# Cell_Balancing_Interface.net
KiCad netlist of a schematic drawn in Altium Designer
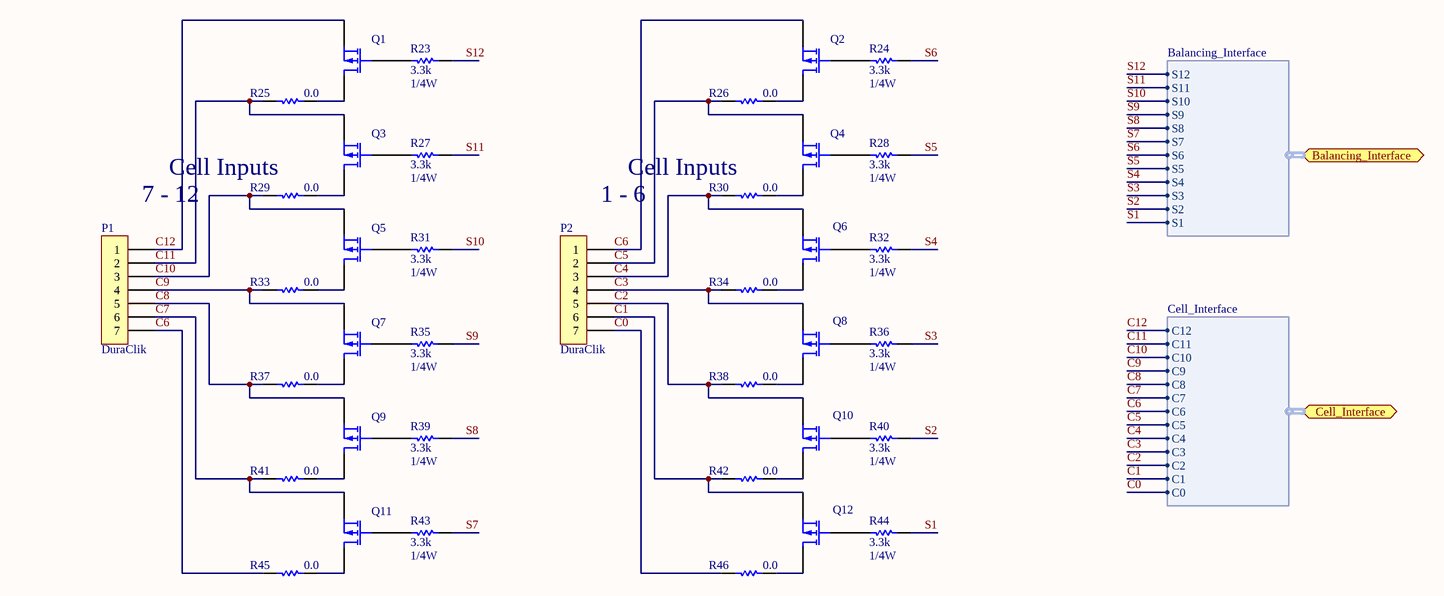
[diagram p0: Cell+Balancing_Interface.SchDoc]

(export (version "E")
  (design (tool "Eeschema 10.0.6"))
  (components
    (comp (ref "P1")
      (value "CONN 7POS DURA-CLIK 0.079\"")
      (description "7 Positions Header Connector 0.079\" (2.00mm) Surface Mount Tin")
      (fields (field (name "SERIES") "DuraClik"))
      (libsource (lib "Schematic Diagrams") (part "CONN 7POS DURA-CLIK 0.079{dblquote}"))
    )
    (comp (ref "P2")
      (value "CONN 7POS DURA-CLIK 0.079\"")
      (description "7 Positions Header Connector 0.079\" (2.00mm) Surface Mount Tin")
      (fields (field (name "SERIES") "DuraClik"))
      (libsource (lib "Schematic Diagrams") (part "CONN 7POS DURA-CLIK 0.079{dblquote}"))
    )
    (comp (ref "Q1")
      (value "MOSFET P-CH 16V 2.5A X2-DFN2015")
      (description "P-Channel 16V 2.5A (Ta) 650mW (Ta) Surface Mount X2-DFN2015-3")
      (libsource (lib "Schematic Diagrams") (part "MOSFET P-CH 16V 2.5A X2-DFN2015"))
    )
    (comp (ref "Q2")
      (value "MOSFET P-CH 16V 2.5A X2-DFN2015")
      (description "P-Channel 16V 2.5A (Ta) 650mW (Ta) Surface Mount X2-DFN2015-3")
      (libsource (lib "Schematic Diagrams") (part "MOSFET P-CH 16V 2.5A X2-DFN2015"))
    )
    (comp (ref "Q3")
      (value "MOSFET P-CH 16V 2.5A X2-DFN2015")
      (description "P-Channel 16V 2.5A (Ta) 650mW (Ta) Surface Mount X2-DFN2015-3")
      (libsource (lib "Schematic Diagrams") (part "MOSFET P-CH 16V 2.5A X2-DFN2015"))
    )
    (comp (ref "Q4")
      (value "MOSFET P-CH 16V 2.5A X2-DFN2015")
      (description "P-Channel 16V 2.5A (Ta) 650mW (Ta) Surface Mount X2-DFN2015-3")
      (libsource (lib "Schematic Diagrams") (part "MOSFET P-CH 16V 2.5A X2-DFN2015"))
    )
    (comp (ref "Q5")
      (value "MOSFET P-CH 16V 2.5A X2-DFN2015")
      (description "P-Channel 16V 2.5A (Ta) 650mW (Ta) Surface Mount X2-DFN2015-3")
      (libsource (lib "Schematic Diagrams") (part "MOSFET P-CH 16V 2.5A X2-DFN2015"))
    )
    (comp (ref "Q6")
      (value "MOSFET P-CH 16V 2.5A X2-DFN2015")
      (description "P-Channel 16V 2.5A (Ta) 650mW (Ta) Surface Mount X2-DFN2015-3")
      (libsource (lib "Schematic Diagrams") (part "MOSFET P-CH 16V 2.5A X2-DFN2015"))
    )
    (comp (ref "Q7")
      (value "MOSFET P-CH 16V 2.5A X2-DFN2015")
      (description "P-Channel 16V 2.5A (Ta) 650mW (Ta) Surface Mount X2-DFN2015-3")
      (libsource (lib "Schematic Diagrams") (part "MOSFET P-CH 16V 2.5A X2-DFN2015"))
    )
    (comp (ref "Q8")
      (value "MOSFET P-CH 16V 2.5A X2-DFN2015")
      (description "P-Channel 16V 2.5A (Ta) 650mW (Ta) Surface Mount X2-DFN2015-3")
      (libsource (lib "Schematic Diagrams") (part "MOSFET P-CH 16V 2.5A X2-DFN2015"))
    )
    (comp (ref "Q9")
      (value "MOSFET P-CH 16V 2.5A X2-DFN2015")
      (description "P-Channel 16V 2.5A (Ta) 650mW (Ta) Surface Mount X2-DFN2015-3")
      (libsource (lib "Schematic Diagrams") (part "MOSFET P-CH 16V 2.5A X2-DFN2015"))
    )
    (comp (ref "Q10")
      (value "MOSFET P-CH 16V 2.5A X2-DFN2015")
      (description "P-Channel 16V 2.5A (Ta) 650mW (Ta) Surface Mount X2-DFN2015-3")
      (libsource (lib "Schematic Diagrams") (part "MOSFET P-CH 16V 2.5A X2-DFN2015"))
    )
    (comp (ref "Q11")
      (value "MOSFET P-CH 16V 2.5A X2-DFN2015")
      (description "P-Channel 16V 2.5A (Ta) 650mW (Ta) Surface Mount X2-DFN2015-3")
      (libsource (lib "Schematic Diagrams") (part "MOSFET P-CH 16V 2.5A X2-DFN2015"))
    )
    (comp (ref "Q12")
      (value "MOSFET P-CH 16V 2.5A X2-DFN2015")
      (description "P-Channel 16V 2.5A (Ta) 650mW (Ta) Surface Mount X2-DFN2015-3")
      (libsource (lib "Schematic Diagrams") (part "MOSFET P-CH 16V 2.5A X2-DFN2015"))
    )
    (comp (ref "R23")
      (value "RES 3.3K OHM 1% 1/4W 0603")
      (footprint "RES, 0603")
      (fields
        (field (name "TOLERANCE") "±1%")
        (field (name "RESISTANCE") "3.3k")
        (field (name "POWER") "1/4W")
      )
      (libsource (lib "Schematic Diagrams") (part "RES 3.3K OHM 1% 1/4W 0603"))
    )
    (comp (ref "R24")
      (value "RES 3.3K OHM 1% 1/4W 0603")
      (footprint "RES, 0603")
      (fields
        (field (name "TOLERANCE") "±1%")
        (field (name "RESISTANCE") "3.3k")
        (field (name "POWER") "1/4W")
      )
      (libsource (lib "Schematic Diagrams") (part "RES 3.3K OHM 1% 1/4W 0603"))
    )
    (comp (ref "R25")
      (value "RES 0.0 OHM 1/4W 0603")
      (footprint "RES, 0603")
      (description "RES SMD 0.0 OHM JUMPER 1/4W 0603")
      (fields (field (name "RESISTANCE") "0.0"))
      (libsource (lib "Schematic Diagrams") (part "RES 0.0 OHM 1/4W 0603"))
    )
    (comp (ref "R26")
      (value "RES 0.0 OHM 1/4W 0603")
      (footprint "RES, 0603")
      (description "RES SMD 0.0 OHM JUMPER 1/4W 0603")
      (fields (field (name "RESISTANCE") "0.0"))
      (libsource (lib "Schematic Diagrams") (part "RES 0.0 OHM 1/4W 0603"))
    )
    (comp (ref "R27")
      (value "RES 3.3K OHM 1% 1/4W 0603")
      (footprint "RES, 0603")
      (fields
        (field (name "TOLERANCE") "±1%")
        (field (name "RESISTANCE") "3.3k")
        (field (name "POWER") "1/4W")
      )
      (libsource (lib "Schematic Diagrams") (part "RES 3.3K OHM 1% 1/4W 0603"))
    )
    (comp (ref "R28")
      (value "RES 3.3K OHM 1% 1/4W 0603")
      (footprint "RES, 0603")
      (fields
        (field (name "TOLERANCE") "±1%")
        (field (name "RESISTANCE") "3.3k")
        (field (name "POWER") "1/4W")
      )
      (libsource (lib "Schematic Diagrams") (part "RES 3.3K OHM 1% 1/4W 0603"))
    )
    (comp (ref "R29")
      (value "RES 0.0 OHM 1/4W 0603")
      (footprint "RES, 0603")
      (description "RES SMD 0.0 OHM JUMPER 1/4W 0603")
      (fields (field (name "RESISTANCE") "0.0"))
      (libsource (lib "Schematic Diagrams") (part "RES 0.0 OHM 1/4W 0603"))
    )
    (comp (ref "R30")
      (value "RES 0.0 OHM 1/4W 0603")
      (footprint "RES, 0603")
      (description "RES SMD 0.0 OHM JUMPER 1/4W 0603")
      (fields (field (name "RESISTANCE") "0.0"))
      (libsource (lib "Schematic Diagrams") (part "RES 0.0 OHM 1/4W 0603"))
    )
    (comp (ref "R31")
      (value "RES 3.3K OHM 1% 1/4W 0603")
      (footprint "RES, 0603")
      (fields
        (field (name "TOLERANCE") "±1%")
        (field (name "RESISTANCE") "3.3k")
        (field (name "POWER") "1/4W")
      )
      (libsource (lib "Schematic Diagrams") (part "RES 3.3K OHM 1% 1/4W 0603"))
    )
    (comp (ref "R32")
      (value "RES 3.3K OHM 1% 1/4W 0603")
      (footprint "RES, 0603")
      (fields
        (field (name "TOLERANCE") "±1%")
        (field (name "RESISTANCE") "3.3k")
        (field (name "POWER") "1/4W")
      )
      (libsource (lib "Schematic Diagrams") (part "RES 3.3K OHM 1% 1/4W 0603"))
    )
    (comp (ref "R33")
      (value "RES 0.0 OHM 1/4W 0603")
      (footprint "RES, 0603")
      (description "RES SMD 0.0 OHM JUMPER 1/4W 0603")
      (fields (field (name "RESISTANCE") "0.0"))
      (libsource (lib "Schematic Diagrams") (part "RES 0.0 OHM 1/4W 0603"))
    )
    (comp (ref "R34")
      (value "RES 0.0 OHM 1/4W 0603")
      (footprint "RES, 0603")
      (description "RES SMD 0.0 OHM JUMPER 1/4W 0603")
      (fields (field (name "RESISTANCE") "0.0"))
      (libsource (lib "Schematic Diagrams") (part "RES 0.0 OHM 1/4W 0603"))
    )
    (comp (ref "R35")
      (value "RES 3.3K OHM 1% 1/4W 0603")
      (footprint "RES, 0603")
      (fields
        (field (name "TOLERANCE") "±1%")
        (field (name "RESISTANCE") "3.3k")
        (field (name "POWER") "1/4W")
      )
      (libsource (lib "Schematic Diagrams") (part "RES 3.3K OHM 1% 1/4W 0603"))
    )
    (comp (ref "R36")
      (value "RES 3.3K OHM 1% 1/4W 0603")
      (footprint "RES, 0603")
      (fields
        (field (name "TOLERANCE") "±1%")
        (field (name "RESISTANCE") "3.3k")
        (field (name "POWER") "1/4W")
      )
      (libsource (lib "Schematic Diagrams") (part "RES 3.3K OHM 1% 1/4W 0603"))
    )
    (comp (ref "R37")
      (value "RES 0.0 OHM 1/4W 0603")
      (footprint "RES, 0603")
      (description "RES SMD 0.0 OHM JUMPER 1/4W 0603")
      (fields (field (name "RESISTANCE") "0.0"))
      (libsource (lib "Schematic Diagrams") (part "RES 0.0 OHM 1/4W 0603"))
    )
    (comp (ref "R38")
      (value "RES 0.0 OHM 1/4W 0603")
      (footprint "RES, 0603")
      (description "RES SMD 0.0 OHM JUMPER 1/4W 0603")
      (fields (field (name "RESISTANCE") "0.0"))
      (libsource (lib "Schematic Diagrams") (part "RES 0.0 OHM 1/4W 0603"))
    )
    (comp (ref "R39")
      (value "RES 3.3K OHM 1% 1/4W 0603")
      (footprint "RES, 0603")
      (fields
        (field (name "TOLERANCE") "±1%")
        (field (name "RESISTANCE") "3.3k")
        (field (name "POWER") "1/4W")
      )
      (libsource (lib "Schematic Diagrams") (part "RES 3.3K OHM 1% 1/4W 0603"))
    )
    (comp (ref "R40")
      (value "RES 3.3K OHM 1% 1/4W 0603")
      (footprint "RES, 0603")
      (fields
        (field (name "TOLERANCE") "±1%")
        (field (name "RESISTANCE") "3.3k")
        (field (name "POWER") "1/4W")
      )
      (libsource (lib "Schematic Diagrams") (part "RES 3.3K OHM 1% 1/4W 0603"))
    )
    (comp (ref "R41")
      (value "RES 0.0 OHM 1/4W 0603")
      (footprint "RES, 0603")
      (description "RES SMD 0.0 OHM JUMPER 1/4W 0603")
      (fields (field (name "RESISTANCE") "0.0"))
      (libsource (lib "Schematic Diagrams") (part "RES 0.0 OHM 1/4W 0603"))
    )
    (comp (ref "R42")
      (value "RES 0.0 OHM 1/4W 0603")
      (footprint "RES, 0603")
      (description "RES SMD 0.0 OHM JUMPER 1/4W 0603")
      (fields (field (name "RESISTANCE") "0.0"))
      (libsource (lib "Schematic Diagrams") (part "RES 0.0 OHM 1/4W 0603"))
    )
    (comp (ref "R43")
      (value "RES 3.3K OHM 1% 1/4W 0603")
      (footprint "RES, 0603")
      (fields
        (field (name "TOLERANCE") "±1%")
        (field (name "RESISTANCE") "3.3k")
        (field (name "POWER") "1/4W")
      )
      (libsource (lib "Schematic Diagrams") (part "RES 3.3K OHM 1% 1/4W 0603"))
    )
    (comp (ref "R44")
      (value "RES 3.3K OHM 1% 1/4W 0603")
      (footprint "RES, 0603")
      (fields
        (field (name "TOLERANCE") "±1%")
        (field (name "RESISTANCE") "3.3k")
        (field (name "POWER") "1/4W")
      )
      (libsource (lib "Schematic Diagrams") (part "RES 3.3K OHM 1% 1/4W 0603"))
    )
    (comp (ref "R45")
      (value "RES 0.0 OHM 1/4W 0603")
      (footprint "RES, 0603")
      (description "RES SMD 0.0 OHM JUMPER 1/4W 0603")
      (fields (field (name "RESISTANCE") "0.0"))
      (libsource (lib "Schematic Diagrams") (part "RES 0.0 OHM 1/4W 0603"))
    )
    (comp (ref "R46")
      (value "RES 0.0 OHM 1/4W 0603")
      (footprint "RES, 0603")
      (description "RES SMD 0.0 OHM JUMPER 1/4W 0603")
      (fields (field (name "RESISTANCE") "0.0"))
      (libsource (lib "Schematic Diagrams") (part "RES 0.0 OHM 1/4W 0603"))
    )
  )
  (nets
    (net (code "3") (name "/C0") (class "Default")
      (node (ref "P2") (pin "7") (pinfunction "7_7") (pintype "passive"))
      (node (ref "R46") (pin "2") (pinfunction "2_2") (pintype "passive"))
    )
    (net (code "4") (name "/C1") (class "Default")
      (node (ref "P2") (pin "6") (pinfunction "6_6") (pintype "passive"))
      (node (ref "Q12") (pin "2") (pinfunction "S_2") (pintype "passive"))
      (node (ref "R42") (pin "2") (pinfunction "2_2") (pintype "passive"))
    )
    (net (code "5") (name "/C2") (class "Default")
      (node (ref "P2") (pin "5") (pinfunction "5_5") (pintype "passive"))
      (node (ref "Q10") (pin "2") (pinfunction "S_2") (pintype "passive"))
      (node (ref "R38") (pin "2") (pinfunction "2_2") (pintype "passive"))
    )
    (net (code "6") (name "/C3") (class "Default")
      (node (ref "P2") (pin "4") (pinfunction "4_4") (pintype "passive"))
      (node (ref "Q8") (pin "2") (pinfunction "S_2") (pintype "passive"))
      (node (ref "R34") (pin "2") (pinfunction "2_2") (pintype "passive"))
    )
    (net (code "7") (name "/C4") (class "Default")
      (node (ref "P2") (pin "3") (pinfunction "3_3") (pintype "passive"))
      (node (ref "Q6") (pin "2") (pinfunction "S_2") (pintype "passive"))
      (node (ref "R30") (pin "2") (pinfunction "2_2") (pintype "passive"))
    )
    (net (code "8") (name "/C5") (class "Default")
      (node (ref "P2") (pin "2") (pinfunction "2_2") (pintype "passive"))
      (node (ref "Q4") (pin "2") (pinfunction "S_2") (pintype "passive"))
      (node (ref "R26") (pin "2") (pinfunction "2_2") (pintype "passive"))
    )
    (net (code "9") (name "/C6") (class "Default")
      (node (ref "P1") (pin "7") (pinfunction "7_7") (pintype "passive"))
      (node (ref "P2") (pin "1") (pinfunction "1_1") (pintype "passive"))
      (node (ref "Q2") (pin "2") (pinfunction "S_2") (pintype "passive"))
      (node (ref "R45") (pin "2") (pinfunction "2_2") (pintype "passive"))
    )
    (net (code "10") (name "/C7") (class "Default")
      (node (ref "P1") (pin "6") (pinfunction "6_6") (pintype "passive"))
      (node (ref "Q11") (pin "2") (pinfunction "S_2") (pintype "passive"))
      (node (ref "R41") (pin "2") (pinfunction "2_2") (pintype "passive"))
    )
    (net (code "11") (name "/C8") (class "Default")
      (node (ref "P1") (pin "5") (pinfunction "5_5") (pintype "passive"))
      (node (ref "Q9") (pin "2") (pinfunction "S_2") (pintype "passive"))
      (node (ref "R37") (pin "2") (pinfunction "2_2") (pintype "passive"))
    )
    (net (code "12") (name "/C9") (class "Default")
      (node (ref "P1") (pin "4") (pinfunction "4_4") (pintype "passive"))
      (node (ref "Q7") (pin "2") (pinfunction "S_2") (pintype "passive"))
      (node (ref "R33") (pin "2") (pinfunction "2_2") (pintype "passive"))
    )
    (net (code "13") (name "/C10") (class "Default")
      (node (ref "P1") (pin "3") (pinfunction "3_3") (pintype "passive"))
      (node (ref "Q5") (pin "2") (pinfunction "S_2") (pintype "passive"))
      (node (ref "R29") (pin "2") (pinfunction "2_2") (pintype "passive"))
    )
    (net (code "14") (name "/C11") (class "Default")
      (node (ref "P1") (pin "2") (pinfunction "2_2") (pintype "passive"))
      (node (ref "Q3") (pin "2") (pinfunction "S_2") (pintype "passive"))
      (node (ref "R25") (pin "2") (pinfunction "2_2") (pintype "passive"))
    )
    (net (code "15") (name "/C12") (class "Default")
      (node (ref "P1") (pin "1") (pinfunction "1_1") (pintype "passive"))
      (node (ref "Q1") (pin "2") (pinfunction "S_2") (pintype "passive"))
    )
    (net (code "16") (name "/S1") (class "Default")
      (node (ref "R44") (pin "1") (pinfunction "1_1") (pintype "passive"))
    )
    (net (code "17") (name "/S2") (class "Default")
      (node (ref "R40") (pin "1") (pinfunction "1_1") (pintype "passive"))
    )
    (net (code "18") (name "/S3") (class "Default")
      (node (ref "R36") (pin "1") (pinfunction "1_1") (pintype "passive"))
    )
    (net (code "19") (name "/S4") (class "Default")
      (node (ref "R32") (pin "1") (pinfunction "1_1") (pintype "passive"))
    )
    (net (code "20") (name "/S5") (class "Default")
      (node (ref "R28") (pin "1") (pinfunction "1_1") (pintype "passive"))
    )
    (net (code "21") (name "/S6") (class "Default")
      (node (ref "R24") (pin "1") (pinfunction "1_1") (pintype "passive"))
    )
    (net (code "22") (name "/S7") (class "Default")
      (node (ref "R43") (pin "1") (pinfunction "1_1") (pintype "passive"))
    )
    (net (code "23") (name "/S8") (class "Default")
      (node (ref "R39") (pin "1") (pinfunction "1_1") (pintype "passive"))
    )
    (net (code "24") (name "/S9") (class "Default")
      (node (ref "R35") (pin "1") (pinfunction "1_1") (pintype "passive"))
    )
    (net (code "25") (name "/S10") (class "Default")
      (node (ref "R31") (pin "1") (pinfunction "1_1") (pintype "passive"))
    )
    (net (code "26") (name "/S11") (class "Default")
      (node (ref "R27") (pin "1") (pinfunction "1_1") (pintype "passive"))
    )
    (net (code "27") (name "/S12") (class "Default")
      (node (ref "R23") (pin "1") (pinfunction "1_1") (pintype "passive"))
    )
    (net (code "30") (name "Net-(Q1-D)") (class "Default")
      (node (ref "Q1") (pin "3") (pinfunction "D_3") (pintype "passive"))
      (node (ref "R25") (pin "1") (pinfunction "1_1") (pintype "passive"))
    )
    (net (code "31") (name "Net-(Q1-G)") (class "Default")
      (node (ref "Q1") (pin "1") (pinfunction "G_1") (pintype "passive"))
      (node (ref "R23") (pin "2") (pinfunction "2_2") (pintype "passive"))
    )
    (net (code "32") (name "Net-(Q2-D)") (class "Default")
      (node (ref "Q2") (pin "3") (pinfunction "D_3") (pintype "passive"))
      (node (ref "R26") (pin "1") (pinfunction "1_1") (pintype "passive"))
    )
    (net (code "33") (name "Net-(Q2-G)") (class "Default")
      (node (ref "Q2") (pin "1") (pinfunction "G_1") (pintype "passive"))
      (node (ref "R24") (pin "2") (pinfunction "2_2") (pintype "passive"))
    )
    (net (code "34") (name "Net-(Q3-D)") (class "Default")
      (node (ref "Q3") (pin "3") (pinfunction "D_3") (pintype "passive"))
      (node (ref "R29") (pin "1") (pinfunction "1_1") (pintype "passive"))
    )
    (net (code "35") (name "Net-(Q3-G)") (class "Default")
      (node (ref "Q3") (pin "1") (pinfunction "G_1") (pintype "passive"))
      (node (ref "R27") (pin "2") (pinfunction "2_2") (pintype "passive"))
    )
    (net (code "36") (name "Net-(Q4-D)") (class "Default")
      (node (ref "Q4") (pin "3") (pinfunction "D_3") (pintype "passive"))
      (node (ref "R30") (pin "1") (pinfunction "1_1") (pintype "passive"))
    )
    (net (code "37") (name "Net-(Q4-G)") (class "Default")
      (node (ref "Q4") (pin "1") (pinfunction "G_1") (pintype "passive"))
      (node (ref "R28") (pin "2") (pinfunction "2_2") (pintype "passive"))
    )
    (net (code "38") (name "Net-(Q5-D)") (class "Default")
      (node (ref "Q5") (pin "3") (pinfunction "D_3") (pintype "passive"))
      (node (ref "R33") (pin "1") (pinfunction "1_1") (pintype "passive"))
    )
    (net (code "39") (name "Net-(Q5-G)") (class "Default")
      (node (ref "Q5") (pin "1") (pinfunction "G_1") (pintype "passive"))
      (node (ref "R31") (pin "2") (pinfunction "2_2") (pintype "passive"))
    )
    (net (code "40") (name "Net-(Q6-D)") (class "Default")
      (node (ref "Q6") (pin "3") (pinfunction "D_3") (pintype "passive"))
      (node (ref "R34") (pin "1") (pinfunction "1_1") (pintype "passive"))
    )
    (net (code "41") (name "Net-(Q6-G)") (class "Default")
      (node (ref "Q6") (pin "1") (pinfunction "G_1") (pintype "passive"))
      (node (ref "R32") (pin "2") (pinfunction "2_2") (pintype "passive"))
    )
    (net (code "42") (name "Net-(Q7-D)") (class "Default")
      (node (ref "Q7") (pin "3") (pinfunction "D_3") (pintype "passive"))
      (node (ref "R37") (pin "1") (pinfunction "1_1") (pintype "passive"))
    )
    (net (code "43") (name "Net-(Q7-G)") (class "Default")
      (node (ref "Q7") (pin "1") (pinfunction "G_1") (pintype "passive"))
      (node (ref "R35") (pin "2") (pinfunction "2_2") (pintype "passive"))
    )
    (net (code "44") (name "Net-(Q8-D)") (class "Default")
      (node (ref "Q8") (pin "3") (pinfunction "D_3") (pintype "passive"))
      (node (ref "R38") (pin "1") (pinfunction "1_1") (pintype "passive"))
    )
    (net (code "45") (name "Net-(Q8-G)") (class "Default")
      (node (ref "Q8") (pin "1") (pinfunction "G_1") (pintype "passive"))
      (node (ref "R36") (pin "2") (pinfunction "2_2") (pintype "passive"))
    )
    (net (code "46") (name "Net-(Q9-D)") (class "Default")
      (node (ref "Q9") (pin "3") (pinfunction "D_3") (pintype "passive"))
      (node (ref "R41") (pin "1") (pinfunction "1_1") (pintype "passive"))
    )
    (net (code "47") (name "Net-(Q9-G)") (class "Default")
      (node (ref "Q9") (pin "1") (pinfunction "G_1") (pintype "passive"))
      (node (ref "R39") (pin "2") (pinfunction "2_2") (pintype "passive"))
    )
    (net (code "48") (name "Net-(Q10-D)") (class "Default")
      (node (ref "Q10") (pin "3") (pinfunction "D_3") (pintype "passive"))
      (node (ref "R42") (pin "1") (pinfunction "1_1") (pintype "passive"))
    )
    (net (code "49") (name "Net-(Q10-G)") (class "Default")
      (node (ref "Q10") (pin "1") (pinfunction "G_1") (pintype "passive"))
      (node (ref "R40") (pin "2") (pinfunction "2_2") (pintype "passive"))
    )
    (net (code "50") (name "Net-(Q11-D)") (class "Default")
      (node (ref "Q11") (pin "3") (pinfunction "D_3") (pintype "passive"))
      (node (ref "R45") (pin "1") (pinfunction "1_1") (pintype "passive"))
    )
    (net (code "51") (name "Net-(Q11-G)") (class "Default")
      (node (ref "Q11") (pin "1") (pinfunction "G_1") (pintype "passive"))
      (node (ref "R43") (pin "2") (pinfunction "2_2") (pintype "passive"))
    )
    (net (code "52") (name "Net-(Q12-D)") (class "Default")
      (node (ref "Q12") (pin "3") (pinfunction "D_3") (pintype "passive"))
      (node (ref "R46") (pin "1") (pinfunction "1_1") (pintype "passive"))
    )
    (net (code "53") (name "Net-(Q12-G)") (class "Default")
      (node (ref "Q12") (pin "1") (pinfunction "G_1") (pintype "passive"))
      (node (ref "R44") (pin "2") (pinfunction "2_2") (pintype "passive"))
    )
  )
)
